# HydrophoneGroup2FilterAndAmpCircuit.net
KiCad netlist of a schematic drawn in Altium Designer
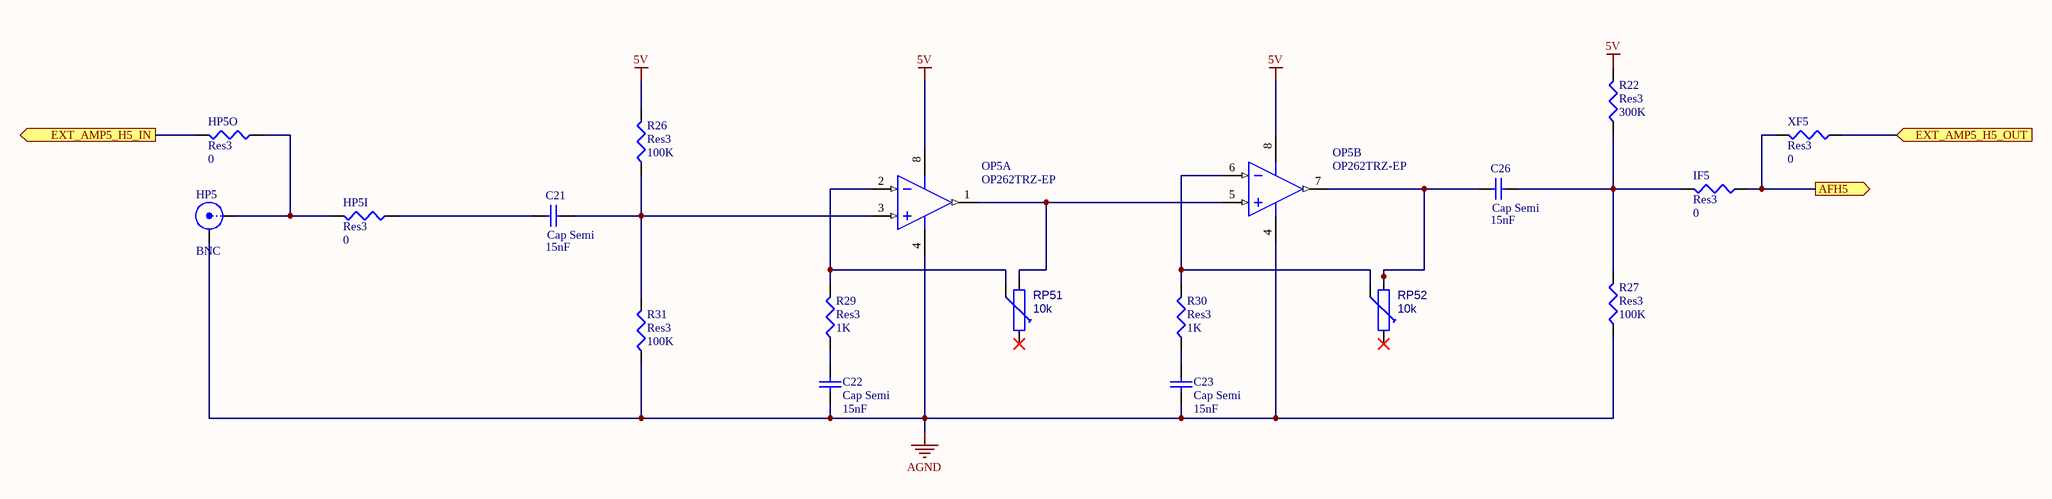
[diagram p0: HydrophoneGroup2FilterAndAmpCircuit.SchDoc]

(export (version "E")
  (design (tool "Eeschema 10.0.6"))
  (components
    (comp (ref "C21")
      (value "Cap Semi")
      (footprint "C0805")
      (description "Capacitor (Semiconductor SIM Model)")
      (fields (field (name "ALTIUM_VALUE") "15nF") (field (name "PUBLISHER") "Altium Limited"))
      (libsource (lib "Miscellaneous Devices") (part "Cap Semi"))
    )
    (comp (ref "C22")
      (value "Cap Semi")
      (footprint "C0805")
      (description "Capacitor (Semiconductor SIM Model)")
      (fields (field (name "ALTIUM_VALUE") "15nF") (field (name "PUBLISHER") "Altium Limited"))
      (libsource (lib "Miscellaneous Devices") (part "Cap Semi"))
    )
    (comp (ref "C23")
      (value "Cap Semi")
      (footprint "C0805")
      (description "Capacitor (Semiconductor SIM Model)")
      (fields (field (name "ALTIUM_VALUE") "15nF") (field (name "PUBLISHER") "Altium Limited"))
      (libsource (lib "Miscellaneous Devices") (part "Cap Semi"))
    )
    (comp (ref "C26")
      (value "Cap Semi")
      (footprint "C0805")
      (description "Capacitor (Semiconductor SIM Model)")
      (fields (field (name "ALTIUM_VALUE") "15nF") (field (name "PUBLISHER") "Altium Limited"))
      (libsource (lib "Miscellaneous Devices") (part "Cap Semi"))
    )
    (comp (ref "HP5")
      (value "BNC")
      (footprint "BNC_RA CON")
      (description "BNC Elbow Connector")
      (fields (field (name "PUBLISHER") "Altium Limited"))
      (libsource (lib "Miscellaneous Connectors") (part "BNC"))
    )
    (comp (ref "HP5I")
      (value "Res3")
      (footprint "J1-0603")
      (description "Resistor")
      (fields (field (name "ALTIUM_VALUE") "0") (field (name "PUBLISHER") "Altium Limited"))
      (libsource (lib "Miscellaneous Devices") (part "Res3"))
    )
    (comp (ref "HP5O")
      (value "Res3")
      (footprint "J1-0603")
      (description "Resistor")
      (fields (field (name "ALTIUM_VALUE") "0") (field (name "PUBLISHER") "Altium Limited"))
      (libsource (lib "Miscellaneous Devices") (part "Res3"))
    )
    (comp (ref "IF5")
      (value "Res3")
      (footprint "J1-0603")
      (description "Resistor")
      (fields (field (name "ALTIUM_VALUE") "0") (field (name "PUBLISHER") "Altium Limited"))
      (libsource (lib "Miscellaneous Devices") (part "Res3"))
    )
    (comp (ref "OP5")
      (value "OP262TRZ-EP")
      (footprint "ADI-R-8_N")
      (fields (field (name "GENERIC PART NUMBER") "OP262") (field (name "MANUFACTURER") "Analog Devices"))
      (libsource (lib "Analog Devices Operational Amplifiers") (part "OP262TRZ-EP"))
    )
    (comp (ref "R22")
      (value "Res3")
      (footprint "J1-0603")
      (description "Resistor")
      (fields (field (name "ALTIUM_VALUE") "300K") (field (name "PUBLISHER") "Altium Limited"))
      (libsource (lib "Miscellaneous Devices") (part "Res3"))
    )
    (comp (ref "R26")
      (value "Res3")
      (footprint "J1-0603")
      (description "Resistor")
      (fields (field (name "ALTIUM_VALUE") "100K") (field (name "PUBLISHER") "Altium Limited"))
      (libsource (lib "Miscellaneous Devices") (part "Res3"))
    )
    (comp (ref "R27")
      (value "Res3")
      (footprint "J1-0603")
      (description "Resistor")
      (fields (field (name "ALTIUM_VALUE") "100K") (field (name "PUBLISHER") "Altium Limited"))
      (libsource (lib "Miscellaneous Devices") (part "Res3"))
    )
    (comp (ref "R29")
      (value "Res3")
      (footprint "J1-0603")
      (description "Resistor")
      (fields (field (name "ALTIUM_VALUE") "1K") (field (name "PUBLISHER") "Altium Limited"))
      (libsource (lib "Miscellaneous Devices") (part "Res3"))
    )
    (comp (ref "R30")
      (value "Res3")
      (footprint "J1-0603")
      (description "Resistor")
      (fields (field (name "ALTIUM_VALUE") "1K") (field (name "PUBLISHER") "Altium Limited"))
      (libsource (lib "Miscellaneous Devices") (part "Res3"))
    )
    (comp (ref "R31")
      (value "Res3")
      (footprint "J1-0603")
      (description "Resistor")
      (fields (field (name "ALTIUM_VALUE") "100K") (field (name "PUBLISHER") "Altium Limited"))
      (libsource (lib "Miscellaneous Devices") (part "Res3"))
    )
    (comp (ref "RP51")
      (value "10k")
      (footprint "Trim_Bourns3296")
      (description "Resistor Trimmer")
      (fields
        (field (name "PART_NUMBER") "RES_Trim_Bourns3296")
        (field (name "MFR PART NUMBER") "Bourns 3296Y-1-xxxLF")
      )
      (libsource (lib "Bourns") (part "RES_Trim"))
    )
    (comp (ref "RP52")
      (value "10k")
      (footprint "Trim_Bourns3296")
      (description "Resistor Trimmer")
      (fields
        (field (name "PART_NUMBER") "RES_Trim_Bourns3296")
        (field (name "MFR PART NUMBER") "Bourns 3296Y-1-xxxLF")
      )
      (libsource (lib "Bourns") (part "RES_Trim"))
    )
    (comp (ref "XF5")
      (value "Res3")
      (footprint "J1-0603")
      (description "Resistor")
      (fields (field (name "ALTIUM_VALUE") "0") (field (name "PUBLISHER") "Altium Limited"))
      (libsource (lib "Miscellaneous Devices") (part "Res3"))
    )
  )
  (nets
    (net (code "1") (name "/AFH5") (class "Default")
      (node (ref "IF5") (pin "1") (pinfunction "1_1") (pintype "passive"))
      (node (ref "XF5") (pin "2") (pinfunction "2_2") (pintype "passive"))
    )
    (net (code "2") (name "/EXT_AMP5_H5_IN") (class "Default")
      (node (ref "HP5O") (pin "2") (pinfunction "2_2") (pintype "passive"))
    )
    (net (code "3") (name "/EXT_AMP5_H5_OUT") (class "Default")
      (node (ref "XF5") (pin "1") (pinfunction "1_1") (pintype "passive"))
    )
    (net (code "4") (name "5V") (class "Default")
      (node (ref "OP5") (pin "8") (pinfunction "+V_8") (pintype "power_in"))
      (node (ref "R22") (pin "2") (pinfunction "2_2") (pintype "passive"))
      (node (ref "R26") (pin "2") (pinfunction "2_2") (pintype "passive"))
    )
    (net (code "5") (name "AGND") (class "Default")
      (node (ref "C22") (pin "1") (pinfunction "1_1") (pintype "passive"))
      (node (ref "C23") (pin "1") (pinfunction "1_1") (pintype "passive"))
      (node (ref "HP5") (pin "2") (pinfunction "Y_2") (pintype "passive"))
      (node (ref "OP5") (pin "4") (pinfunction "-V_4") (pintype "power_in"))
      (node (ref "R27") (pin "1") (pinfunction "1_1") (pintype "passive"))
      (node (ref "R31") (pin "1") (pinfunction "1_1") (pintype "passive"))
    )
    (net (code "6") (name "Net-(C21-Pad1)") (class "Default")
      (node (ref "C21") (pin "1") (pinfunction "1_1") (pintype "passive"))
      (node (ref "HP5I") (pin "1") (pinfunction "1_1") (pintype "passive"))
    )
    (net (code "7") (name "Net-(C22-Pad2)") (class "Default")
      (node (ref "C22") (pin "2") (pinfunction "2_2") (pintype "passive"))
      (node (ref "R29") (pin "1") (pinfunction "1_1") (pintype "passive"))
    )
    (net (code "8") (name "Net-(C23-Pad2)") (class "Default")
      (node (ref "C23") (pin "2") (pinfunction "2_2") (pintype "passive"))
      (node (ref "R30") (pin "1") (pinfunction "1_1") (pintype "passive"))
    )
    (net (code "9") (name "Net-(C26-Pad2)") (class "Default")
      (node (ref "C26") (pin "2") (pinfunction "2_2") (pintype "passive"))
      (node (ref "IF5") (pin "2") (pinfunction "2_2") (pintype "passive"))
      (node (ref "R22") (pin "1") (pinfunction "1_1") (pintype "passive"))
      (node (ref "R27") (pin "2") (pinfunction "2_2") (pintype "passive"))
    )
    (net (code "10") (name "Net-(HP5-X)") (class "Default")
      (node (ref "HP5") (pin "1") (pinfunction "X_1") (pintype "passive"))
      (node (ref "HP5I") (pin "2") (pinfunction "2_2") (pintype "passive"))
      (node (ref "HP5O") (pin "1") (pinfunction "1_1") (pintype "passive"))
    )
    (net (code "11") (name "Net-(OP5A-+IN_A)") (class "Default")
      (node (ref "C21") (pin "2") (pinfunction "2_2") (pintype "passive"))
      (node (ref "OP5") (pin "3") (pinfunction "+IN_A_3") (pintype "input"))
      (node (ref "R26") (pin "1") (pinfunction "1_1") (pintype "passive"))
      (node (ref "R31") (pin "2") (pinfunction "2_2") (pintype "passive"))
    )
    (net (code "12") (name "Net-(OP5A--IN_A)") (class "Default")
      (node (ref "OP5") (pin "2") (pinfunction "-IN_A_2") (pintype "input"))
      (node (ref "R29") (pin "2") (pinfunction "2_2") (pintype "passive"))
      (node (ref "RP51") (pin "2") (pinfunction "2_2") (pintype "passive"))
    )
    (net (code "13") (name "Net-(OP5A-OUT_A)") (class "Default")
      (node (ref "OP5") (pin "1") (pinfunction "OUT_A_1") (pintype "output"))
      (node (ref "OP5") (pin "5") (pinfunction "+IN_B_5") (pintype "input"))
      (node (ref "RP51") (pin "1") (pinfunction "1_1") (pintype "passive"))
    )
    (net (code "14") (name "Net-(OP5B--IN_B)") (class "Default")
      (node (ref "OP5") (pin "6") (pinfunction "-IN_B_6") (pintype "input"))
      (node (ref "R30") (pin "2") (pinfunction "2_2") (pintype "passive"))
      (node (ref "RP52") (pin "2") (pinfunction "2_2") (pintype "passive"))
    )
    (net (code "15") (name "Net-(OP5B-OUT_B)") (class "Default")
      (node (ref "C26") (pin "1") (pinfunction "1_1") (pintype "passive"))
      (node (ref "OP5") (pin "7") (pinfunction "OUT_B_7") (pintype "output"))
      (node (ref "RP52") (pin "1") (pinfunction "1_1") (pintype "passive"))
    )
    (net (code "16") (name "unconnected-(RP51-Pad3)") (class "Default")
      (node (ref "RP51") (pin "3") (pinfunction "3_3") (pintype "passive+no_connect"))
    )
    (net (code "17") (name "unconnected-(RP52-Pad3)") (class "Default")
      (node (ref "RP52") (pin "3") (pinfunction "3_3") (pintype "passive+no_connect"))
    )
  )
)
